# cube_bottom_1.net
KiCad netlist of a schematic drawn in EAGLE
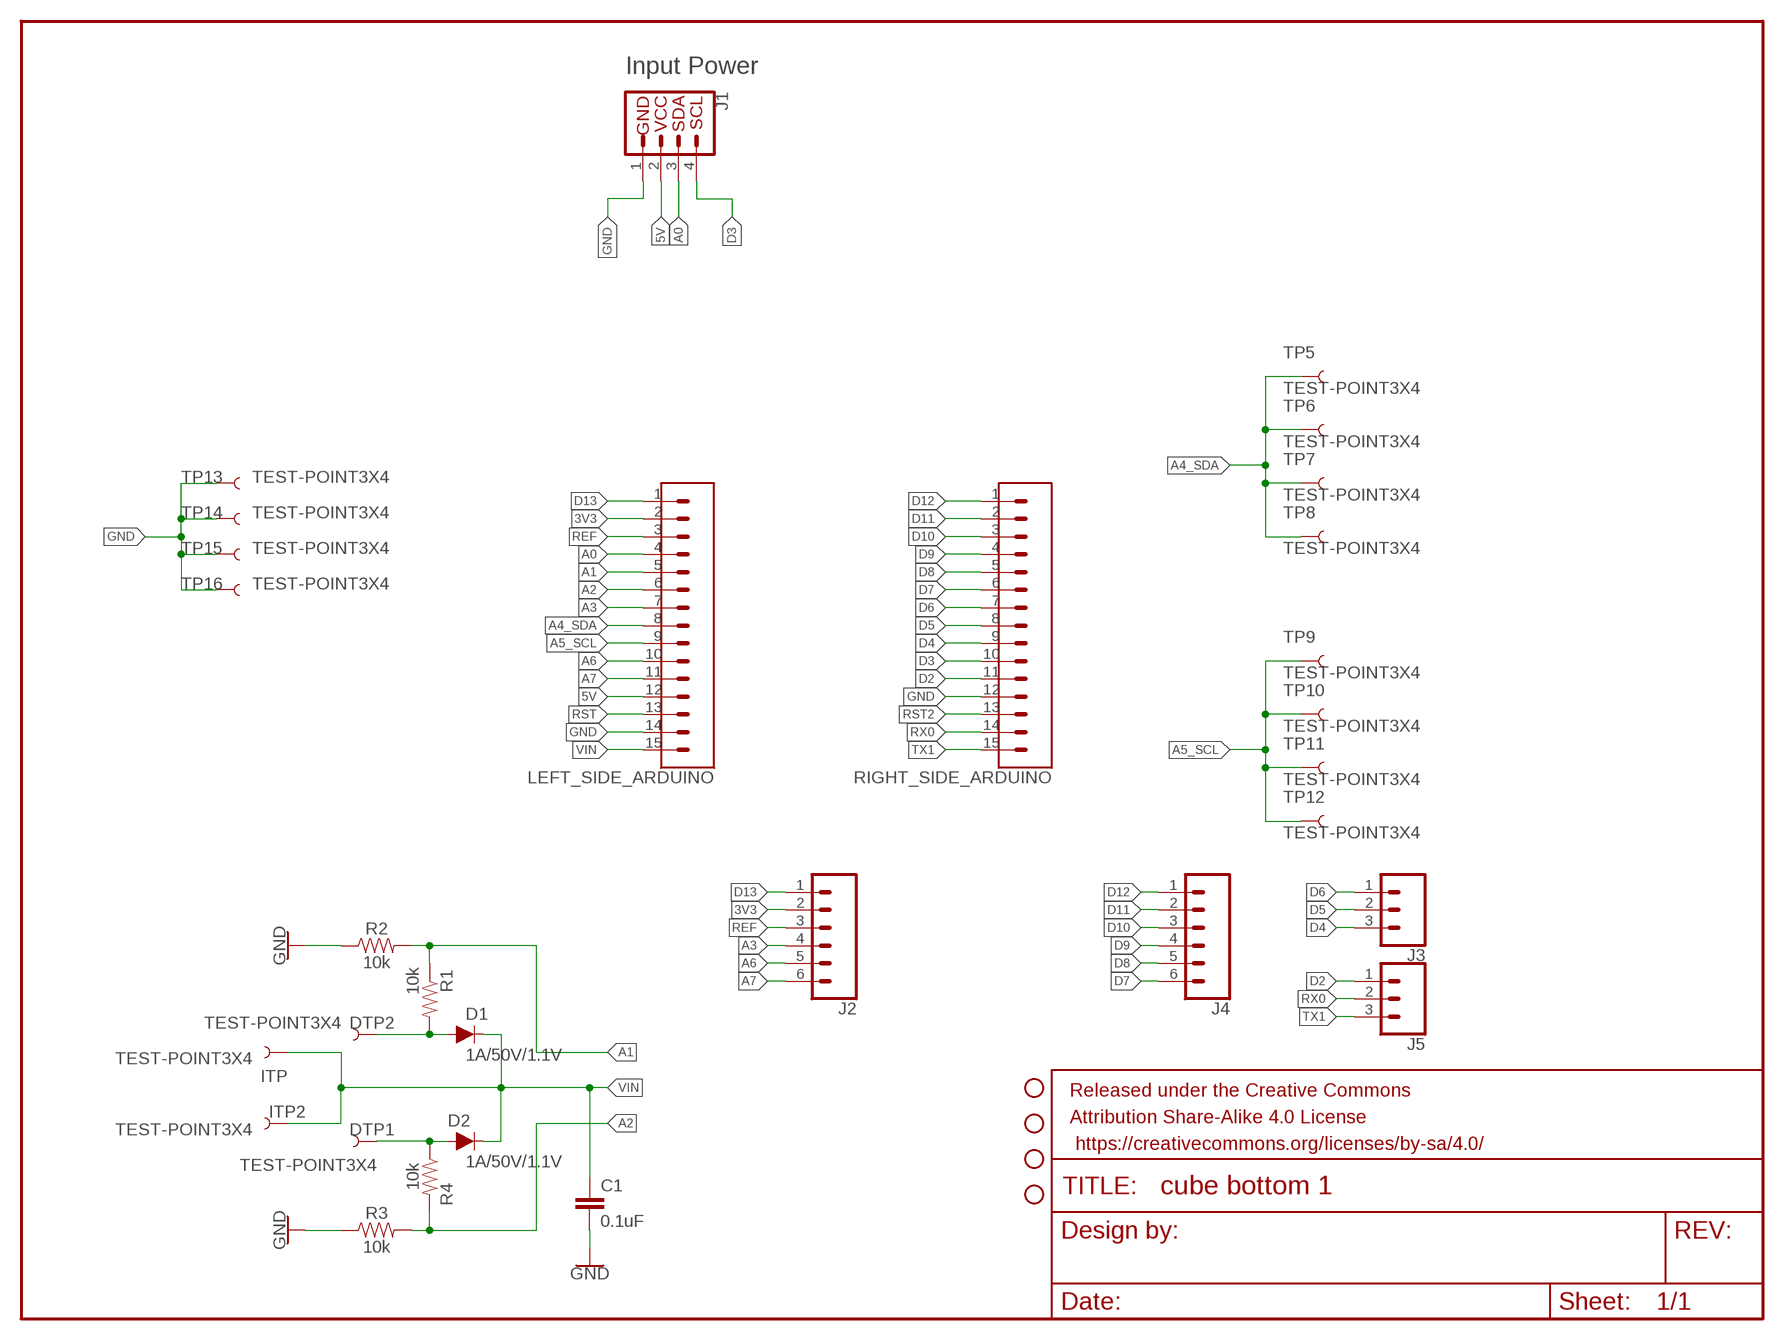
[diagram p0: schematic, sheet 1]

(export (version "E")
  (design (tool "Eeschema 10.0.6"))
  (components
    (comp (ref "C1")
      (value "0.1uF")
      (footprint "eagle-import:0603")
      (libsource (lib "eagle-import") (part "0.1UF-0603-25V-5%"))
    )
    (comp (ref "D1")
      (value "1A/50V/1.1V")
      (footprint "eagle-import:DIODE-1N4001")
      (libsource (lib "eagle-import") (part "DIODE-PTH"))
    )
    (comp (ref "D2")
      (value "1A/50V/1.1V")
      (footprint "eagle-import:DIODE-1N4001")
      (libsource (lib "eagle-import") (part "DIODE-PTH"))
    )
    (comp (ref "DTP1")
      (value "TEST-POINT3X4")
      (footprint "eagle-import:PAD.03X.04")
      (libsource (lib "eagle-import") (part "TEST-POINT3X4"))
    )
    (comp (ref "DTP2")
      (value "TEST-POINT3X4")
      (footprint "eagle-import:PAD.03X.04")
      (libsource (lib "eagle-import") (part "TEST-POINT3X4"))
    )
    (comp (ref "FRAME1")
      (value "FRAME-LETTERNO_PACKAGE")
      (footprint "eagle-import:DUMMY")
      (fields (field (name "DESIGNER") "Nobody"))
      (libsource (lib "eagle-import") (part "FRAME-LETTERNO_PACKAGE"))
    )
    (comp (ref "H1")
      (value "STAND-OFF")
      (footprint "eagle-import:STAND-OFF")
      (libsource (lib "eagle-import") (part "STAND-OFF"))
    )
    (comp (ref "H2")
      (value "STAND-OFF")
      (footprint "eagle-import:STAND-OFF")
      (libsource (lib "eagle-import") (part "STAND-OFF"))
    )
    (comp (ref "H3")
      (value "STAND-OFF")
      (footprint "eagle-import:STAND-OFF")
      (libsource (lib "eagle-import") (part "STAND-OFF"))
    )
    (comp (ref "H4")
      (value "STAND-OFF")
      (footprint "eagle-import:STAND-OFF")
      (libsource (lib "eagle-import") (part "STAND-OFF"))
    )
    (comp (ref "ITP")
      (value "TEST-POINT3X4")
      (footprint "eagle-import:PAD.03X.04")
      (libsource (lib "eagle-import") (part "TEST-POINT3X4"))
    )
    (comp (ref "ITP2")
      (value "TEST-POINT3X4")
      (footprint "eagle-import:PAD.03X.04")
      (libsource (lib "eagle-import") (part "TEST-POINT3X4"))
    )
    (comp (ref "J1")
      (value "QWIIC_CONNECTORJS-1MM")
      (footprint "eagle-import:1X04_1MM_RA")
      (libsource (lib "eagle-import") (part "QWIIC_CONNECTORJS-1MM"))
    )
    (comp (ref "J2")
      (value "CONN_06SILK_FEMALE_PTH")
      (footprint "eagle-import:1X06")
      (libsource (lib "eagle-import") (part "CONN_06SILK_FEMALE_PTH"))
    )
    (comp (ref "J3")
      (value "CONN_03")
      (footprint "eagle-import:1X03")
      (libsource (lib "eagle-import") (part "CONN_03"))
    )
    (comp (ref "J4")
      (value "CONN_06SILK_FEMALE_PTH")
      (footprint "eagle-import:1X06")
      (libsource (lib "eagle-import") (part "CONN_06SILK_FEMALE_PTH"))
    )
    (comp (ref "J5")
      (value "CONN_03")
      (footprint "eagle-import:1X03")
      (libsource (lib "eagle-import") (part "CONN_03"))
    )
    (comp (ref "LEFT_SIDE_ARDUINO")
      (value "CONN_06SMD_MALE")
      (footprint "eagle-import:1X15_SMD_MALE")
      (libsource (lib "eagle-import") (part "capstone footprints_CONN_06SMD_MALE"))
    )
    (comp (ref "R1")
      (value "10k")
      (footprint "eagle-import:0603")
      (libsource (lib "eagle-import") (part "10KOHM-0603-1/10W-1%"))
    )
    (comp (ref "R2")
      (value "10k")
      (footprint "eagle-import:0603")
      (libsource (lib "eagle-import") (part "10KOHM-0603-1/10W-1%"))
    )
    (comp (ref "R3")
      (value "10k")
      (footprint "eagle-import:0603")
      (libsource (lib "eagle-import") (part "10KOHM-0603-1/10W-1%"))
    )
    (comp (ref "R4")
      (value "10k")
      (footprint "eagle-import:0603")
      (libsource (lib "eagle-import") (part "10KOHM-0603-1/10W-1%"))
    )
    (comp (ref "RIGHT_SIDE_ARDUINO")
      (value "CONN_06SMD_MALE")
      (footprint "eagle-import:1X15_SMD_MALE")
      (libsource (lib "eagle-import") (part "capstone footprints_CONN_06SMD_MALE"))
    )
    (comp (ref "TP5")
      (value "TEST-POINT3X4")
      (footprint "eagle-import:PAD.03X.04")
      (libsource (lib "eagle-import") (part "TEST-POINT3X4"))
    )
    (comp (ref "TP6")
      (value "TEST-POINT3X4")
      (footprint "eagle-import:PAD.03X.04")
      (libsource (lib "eagle-import") (part "TEST-POINT3X4"))
    )
    (comp (ref "TP7")
      (value "TEST-POINT3X4")
      (footprint "eagle-import:PAD.03X.04")
      (libsource (lib "eagle-import") (part "TEST-POINT3X4"))
    )
    (comp (ref "TP8")
      (value "TEST-POINT3X4")
      (footprint "eagle-import:PAD.03X.04")
      (libsource (lib "eagle-import") (part "TEST-POINT3X4"))
    )
    (comp (ref "TP9")
      (value "TEST-POINT3X4")
      (footprint "eagle-import:PAD.03X.04")
      (libsource (lib "eagle-import") (part "TEST-POINT3X4"))
    )
    (comp (ref "TP10")
      (value "TEST-POINT3X4")
      (footprint "eagle-import:PAD.03X.04")
      (libsource (lib "eagle-import") (part "TEST-POINT3X4"))
    )
    (comp (ref "TP11")
      (value "TEST-POINT3X4")
      (footprint "eagle-import:PAD.03X.04")
      (libsource (lib "eagle-import") (part "TEST-POINT3X4"))
    )
    (comp (ref "TP12")
      (value "TEST-POINT3X4")
      (footprint "eagle-import:PAD.03X.04")
      (libsource (lib "eagle-import") (part "TEST-POINT3X4"))
    )
    (comp (ref "TP13")
      (value "TEST-POINT3X4")
      (footprint "eagle-import:PAD.03X.04")
      (libsource (lib "eagle-import") (part "TEST-POINT3X4"))
    )
    (comp (ref "TP14")
      (value "TEST-POINT3X4")
      (footprint "eagle-import:PAD.03X.04")
      (libsource (lib "eagle-import") (part "TEST-POINT3X4"))
    )
    (comp (ref "TP15")
      (value "TEST-POINT3X4")
      (footprint "eagle-import:PAD.03X.04")
      (libsource (lib "eagle-import") (part "TEST-POINT3X4"))
    )
    (comp (ref "TP16")
      (value "TEST-POINT3X4")
      (footprint "eagle-import:PAD.03X.04")
      (libsource (lib "eagle-import") (part "TEST-POINT3X4"))
    )
  )
  (nets
    (net (code "1") (name "3V3") (class "Default")
      (node (ref "J2") (pin "2") (pinfunction "2_2") (pintype "passive"))
      (node (ref "LEFT_SIDE_ARDUINO") (pin "2") (pinfunction "2_2") (pintype "passive"))
    )
    (net (code "2") (name "5V") (class "Default")
      (node (ref "J1") (pin "2") (pinfunction "VCC_2") (pintype "power_in"))
      (node (ref "LEFT_SIDE_ARDUINO") (pin "12") (pinfunction "12_12") (pintype "passive"))
    )
    (net (code "3") (name "A0") (class "Default")
      (node (ref "J1") (pin "3") (pinfunction "SDA_3") (pintype "passive"))
      (node (ref "LEFT_SIDE_ARDUINO") (pin "4") (pinfunction "4_4") (pintype "passive"))
    )
    (net (code "4") (name "A1") (class "Default")
      (node (ref "LEFT_SIDE_ARDUINO") (pin "5") (pinfunction "5_5") (pintype "passive"))
      (node (ref "R1") (pin "1") (pinfunction "1_1") (pintype "passive"))
      (node (ref "R2") (pin "2") (pinfunction "2_2") (pintype "passive"))
    )
    (net (code "5") (name "A2") (class "Default")
      (node (ref "LEFT_SIDE_ARDUINO") (pin "6") (pinfunction "6_6") (pintype "passive"))
      (node (ref "R3") (pin "2") (pinfunction "2_2") (pintype "passive"))
      (node (ref "R4") (pin "2") (pinfunction "2_2") (pintype "passive"))
    )
    (net (code "6") (name "A3") (class "Default")
      (node (ref "J2") (pin "4") (pinfunction "4_4") (pintype "passive"))
      (node (ref "LEFT_SIDE_ARDUINO") (pin "7") (pinfunction "7_7") (pintype "passive"))
    )
    (net (code "7") (name "A4_SDA") (class "Default")
      (node (ref "LEFT_SIDE_ARDUINO") (pin "8") (pinfunction "8_8") (pintype "passive"))
      (node (ref "TP5") (pin "P$1") (pinfunction "1_P$1") (pintype "bidirectional"))
      (node (ref "TP6") (pin "P$1") (pinfunction "1_P$1") (pintype "bidirectional"))
      (node (ref "TP7") (pin "P$1") (pinfunction "1_P$1") (pintype "bidirectional"))
      (node (ref "TP8") (pin "P$1") (pinfunction "1_P$1") (pintype "bidirectional"))
    )
    (net (code "8") (name "A5_SCL") (class "Default")
      (node (ref "LEFT_SIDE_ARDUINO") (pin "9") (pinfunction "9_9") (pintype "passive"))
      (node (ref "TP10") (pin "P$1") (pinfunction "1_P$1") (pintype "bidirectional"))
      (node (ref "TP11") (pin "P$1") (pinfunction "1_P$1") (pintype "bidirectional"))
      (node (ref "TP12") (pin "P$1") (pinfunction "1_P$1") (pintype "bidirectional"))
      (node (ref "TP9") (pin "P$1") (pinfunction "1_P$1") (pintype "bidirectional"))
    )
    (net (code "9") (name "A6") (class "Default")
      (node (ref "J2") (pin "5") (pinfunction "5_5") (pintype "passive"))
      (node (ref "LEFT_SIDE_ARDUINO") (pin "10") (pinfunction "10_10") (pintype "passive"))
    )
    (net (code "10") (name "A7") (class "Default")
      (node (ref "J2") (pin "6") (pinfunction "6_6") (pintype "passive"))
      (node (ref "LEFT_SIDE_ARDUINO") (pin "11") (pinfunction "11_11") (pintype "passive"))
    )
    (net (code "11") (name "D2") (class "Default")
      (node (ref "J5") (pin "1") (pinfunction "1_1") (pintype "passive"))
      (node (ref "RIGHT_SIDE_ARDUINO") (pin "11") (pinfunction "11_11") (pintype "passive"))
    )
    (net (code "12") (name "D3") (class "Default")
      (node (ref "J1") (pin "4") (pinfunction "SCL_4") (pintype "passive"))
      (node (ref "RIGHT_SIDE_ARDUINO") (pin "10") (pinfunction "10_10") (pintype "passive"))
    )
    (net (code "13") (name "D4") (class "Default")
      (node (ref "J3") (pin "3") (pinfunction "3_3") (pintype "passive"))
      (node (ref "RIGHT_SIDE_ARDUINO") (pin "9") (pinfunction "9_9") (pintype "passive"))
    )
    (net (code "14") (name "D5") (class "Default")
      (node (ref "J3") (pin "2") (pinfunction "2_2") (pintype "passive"))
      (node (ref "RIGHT_SIDE_ARDUINO") (pin "8") (pinfunction "8_8") (pintype "passive"))
    )
    (net (code "15") (name "D6") (class "Default")
      (node (ref "J3") (pin "1") (pinfunction "1_1") (pintype "passive"))
      (node (ref "RIGHT_SIDE_ARDUINO") (pin "7") (pinfunction "7_7") (pintype "passive"))
    )
    (net (code "16") (name "D7") (class "Default")
      (node (ref "J4") (pin "6") (pinfunction "6_6") (pintype "passive"))
      (node (ref "RIGHT_SIDE_ARDUINO") (pin "6") (pinfunction "6_6") (pintype "passive"))
    )
    (net (code "17") (name "D8") (class "Default")
      (node (ref "J4") (pin "5") (pinfunction "5_5") (pintype "passive"))
      (node (ref "RIGHT_SIDE_ARDUINO") (pin "5") (pinfunction "5_5") (pintype "passive"))
    )
    (net (code "18") (name "D9") (class "Default")
      (node (ref "J4") (pin "4") (pinfunction "4_4") (pintype "passive"))
      (node (ref "RIGHT_SIDE_ARDUINO") (pin "4") (pinfunction "4_4") (pintype "passive"))
    )
    (net (code "19") (name "D10") (class "Default")
      (node (ref "J4") (pin "3") (pinfunction "3_3") (pintype "passive"))
      (node (ref "RIGHT_SIDE_ARDUINO") (pin "3") (pinfunction "3_3") (pintype "passive"))
    )
    (net (code "20") (name "D11") (class "Default")
      (node (ref "J4") (pin "2") (pinfunction "2_2") (pintype "passive"))
      (node (ref "RIGHT_SIDE_ARDUINO") (pin "2") (pinfunction "2_2") (pintype "passive"))
    )
    (net (code "21") (name "D12") (class "Default")
      (node (ref "J4") (pin "1") (pinfunction "1_1") (pintype "passive"))
      (node (ref "RIGHT_SIDE_ARDUINO") (pin "1") (pinfunction "1_1") (pintype "passive"))
    )
    (net (code "22") (name "D13") (class "Default")
      (node (ref "J2") (pin "1") (pinfunction "1_1") (pintype "passive"))
      (node (ref "LEFT_SIDE_ARDUINO") (pin "1") (pinfunction "1_1") (pintype "passive"))
    )
    (net (code "23") (name "GND") (class "Default")
      (node (ref "C1") (pin "2") (pinfunction "2_2") (pintype "passive"))
      (node (ref "J1") (pin "1") (pinfunction "GND_1") (pintype "power_in"))
      (node (ref "LEFT_SIDE_ARDUINO") (pin "14") (pinfunction "14_14") (pintype "passive"))
      (node (ref "R2") (pin "1") (pinfunction "1_1") (pintype "passive"))
      (node (ref "R3") (pin "1") (pinfunction "1_1") (pintype "passive"))
      (node (ref "RIGHT_SIDE_ARDUINO") (pin "12") (pinfunction "12_12") (pintype "passive"))
      (node (ref "TP13") (pin "P$1") (pinfunction "1_P$1") (pintype "bidirectional"))
      (node (ref "TP14") (pin "P$1") (pinfunction "1_P$1") (pintype "bidirectional"))
      (node (ref "TP15") (pin "P$1") (pinfunction "1_P$1") (pintype "bidirectional"))
      (node (ref "TP16") (pin "P$1") (pinfunction "1_P$1") (pintype "bidirectional"))
    )
    (net (code "24") (name "Net-(DTP1-1)") (class "Default")
      (node (ref "D2") (pin "A") (pinfunction "A_A") (pintype "passive"))
      (node (ref "DTP1") (pin "P$1") (pinfunction "1_P$1") (pintype "bidirectional"))
      (node (ref "R4") (pin "1") (pinfunction "1_1") (pintype "passive"))
    )
    (net (code "25") (name "Net-(DTP2-1)") (class "Default")
      (node (ref "D1") (pin "A") (pinfunction "A_A") (pintype "passive"))
      (node (ref "DTP2") (pin "P$1") (pinfunction "1_P$1") (pintype "bidirectional"))
      (node (ref "R1") (pin "2") (pinfunction "2_2") (pintype "passive"))
    )
    (net (code "26") (name "REF") (class "Default")
      (node (ref "J2") (pin "3") (pinfunction "3_3") (pintype "passive"))
      (node (ref "LEFT_SIDE_ARDUINO") (pin "3") (pinfunction "3_3") (pintype "passive"))
    )
    (net (code "27") (name "RST") (class "Default")
      (node (ref "LEFT_SIDE_ARDUINO") (pin "13") (pinfunction "13_13") (pintype "passive"))
    )
    (net (code "28") (name "RST2") (class "Default")
      (node (ref "RIGHT_SIDE_ARDUINO") (pin "13") (pinfunction "13_13") (pintype "passive"))
    )
    (net (code "29") (name "RX0") (class "Default")
      (node (ref "J5") (pin "2") (pinfunction "2_2") (pintype "passive"))
      (node (ref "RIGHT_SIDE_ARDUINO") (pin "14") (pinfunction "14_14") (pintype "passive"))
    )
    (net (code "30") (name "TX1") (class "Default")
      (node (ref "J5") (pin "3") (pinfunction "3_3") (pintype "passive"))
      (node (ref "RIGHT_SIDE_ARDUINO") (pin "15") (pinfunction "15_15") (pintype "passive"))
    )
    (net (code "31") (name "VIN") (class "Default")
      (node (ref "C1") (pin "1") (pinfunction "1_1") (pintype "passive"))
      (node (ref "D1") (pin "C") (pinfunction "C_C") (pintype "passive"))
      (node (ref "D2") (pin "C") (pinfunction "C_C") (pintype "passive"))
      (node (ref "ITP") (pin "P$1") (pinfunction "1_P$1") (pintype "bidirectional"))
      (node (ref "ITP2") (pin "P$1") (pinfunction "1_P$1") (pintype "bidirectional"))
      (node (ref "LEFT_SIDE_ARDUINO") (pin "15") (pinfunction "15_15") (pintype "passive"))
    )
  )
)
